# main_for_huzzah_wLED.net
KiCad netlist of a schematic drawn in EAGLE
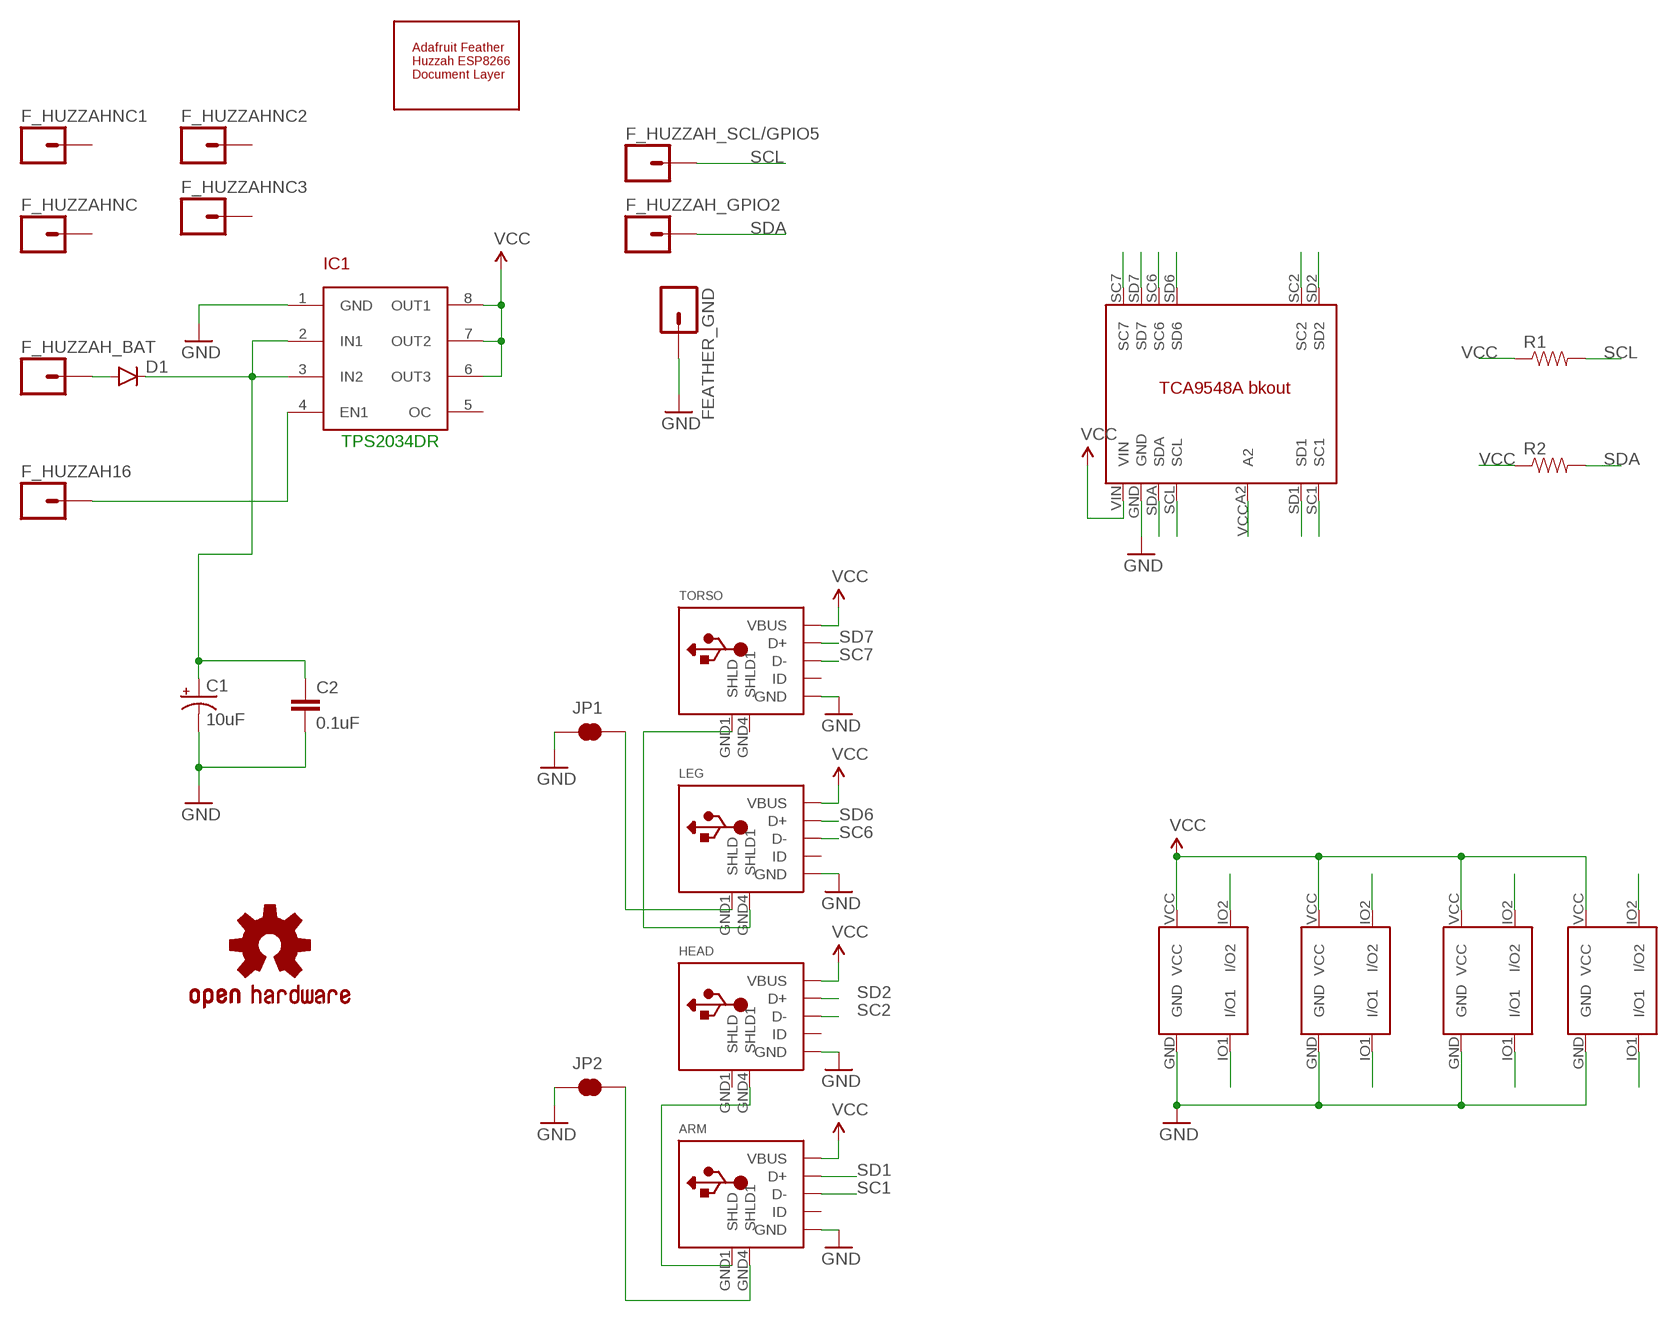
[diagram p0: schematic, sheet 1]

(export (version "E")
  (design (tool "Eeschema 10.0.6"))
  (components
    (comp (ref "ARM")
      (value "USB")
      (footprint "eagle-import:USB-MINIB-THM-MOLEX_NOSLK")
      (libsource (lib "eagle-import") (part "USB"))
    )
    (comp (ref "C1")
      (value "10uF")
      (footprint "eagle-import:CPOL-RADIAL-10UF-25V")
      (libsource (lib "eagle-import") (part "CAP_POLPTH2"))
    )
    (comp (ref "C2")
      (value "0.1uF")
      (footprint "eagle-import:CAP-PTH-SMALL")
      (libsource (lib "eagle-import") (part "CAPPTH"))
    )
    (comp (ref "D1")
      (value "DIODEKIT2")
      (footprint "eagle-import:DIODE-1N4001-KIT")
      (libsource (lib "eagle-import") (part "DIODEKIT2"))
    )
    (comp (ref "FEATHER_GND")
      (value "M01")
      (footprint "eagle-import:1X01SMALL_NS")
      (libsource (lib "eagle-import") (part "M01"))
    )
    (comp (ref "F_HUZZAH16")
      (value "M01")
      (footprint "eagle-import:1X01SMALL_NS")
      (libsource (lib "eagle-import") (part "M01"))
    )
    (comp (ref "F_HUZZAHNC")
      (value "M01")
      (footprint "eagle-import:1X01SMALL_NS")
      (libsource (lib "eagle-import") (part "M01"))
    )
    (comp (ref "F_HUZZAHNC1")
      (value "M01")
      (footprint "eagle-import:1X01SMALL_NS")
      (libsource (lib "eagle-import") (part "M01"))
    )
    (comp (ref "F_HUZZAHNC2")
      (value "M01")
      (footprint "eagle-import:1X01SMALL_NS")
      (libsource (lib "eagle-import") (part "M01"))
    )
    (comp (ref "F_HUZZAHNC3")
      (value "M01")
      (footprint "eagle-import:1X01SMALL_NS")
      (libsource (lib "eagle-import") (part "M01"))
    )
    (comp (ref "F_HUZZAH_BAT")
      (value "M01")
      (footprint "eagle-import:1X01SMALL_NS")
      (libsource (lib "eagle-import") (part "M01"))
    )
    (comp (ref "F_HUZZAH_GPIO2")
      (value "M01")
      (footprint "eagle-import:1X01SMALL_NS")
      (libsource (lib "eagle-import") (part "M01"))
    )
    (comp (ref "F_HUZZAH_SCL/GPIO5")
      (value "M01")
      (footprint "eagle-import:1X01SMALL_NS")
      (libsource (lib "eagle-import") (part "M01"))
    )
    (comp (ref "HEAD")
      (value "USB")
      (footprint "eagle-import:USB-MINIB-THM-MOLEX_NOSLK")
      (libsource (lib "eagle-import") (part "USB"))
    )
    (comp (ref "IC1")
      (value "TPS2055A")
      (footprint "eagle-import:SO-08")
      (libsource (lib "eagle-import") (part "TPS2055A"))
    )
    (comp (ref "JP1")
      (value "JUMPER-PAD-2-NC_BY_TRACENO_SILK")
      (footprint "eagle-import:PAD-JUMPER-2-NC_BY_TRACE_NO_SILK")
      (libsource (lib "eagle-import") (part "JUMPER-PAD-2-NC_BY_TRACENO_SILK"))
    )
    (comp (ref "JP2")
      (value "JUMPER-PAD-2-NC_BY_TRACENO_SILK")
      (footprint "eagle-import:PAD-JUMPER-2-NC_BY_TRACE_NO_SILK")
      (libsource (lib "eagle-import") (part "JUMPER-PAD-2-NC_BY_TRACENO_SILK"))
    )
    (comp (ref "LEG")
      (value "USB")
      (footprint "eagle-import:USB-MINIB-THM-MOLEX_NOSLK")
      (libsource (lib "eagle-import") (part "USB"))
    )
    (comp (ref "LOGO1")
      (value "OSHW-LOGOM")
      (footprint "eagle-import:OSHW-LOGO-M")
      (libsource (lib "eagle-import") (part "OSHW-LOGOM"))
    )
    (comp (ref "R1")
      (value "RESISTORAXIAL-0.3")
      (footprint "eagle-import:AXIAL-0.3")
      (libsource (lib "eagle-import") (part "RESISTORAXIAL-0.3"))
    )
    (comp (ref "R2")
      (value "RESISTORAXIAL-0.3")
      (footprint "eagle-import:AXIAL-0.3")
      (libsource (lib "eagle-import") (part "RESISTORAXIAL-0.3"))
    )
    (comp (ref "TORSO")
      (value "USB")
      (footprint "eagle-import:USB-MINIB-THM-MOLEX_NOSLK")
      (libsource (lib "eagle-import") (part "USB"))
    )
    (comp (ref "U$1")
      (value "TCA9548_MIN")
      (footprint "eagle-import:TCA9548_NOEXTRA")
      (libsource (lib "eagle-import") (part "TCA9548_MIN"))
    )
    (comp (ref "U$2")
      (value "TVS_ARRAY_CD143A")
      (footprint "eagle-import:SOT-143")
      (libsource (lib "eagle-import") (part "TVS_ARRAY_CD143A"))
    )
    (comp (ref "U$3")
      (value "TVS_ARRAY_CD143A")
      (footprint "eagle-import:SOT-143")
      (libsource (lib "eagle-import") (part "TVS_ARRAY_CD143A"))
    )
    (comp (ref "U$4")
      (value "TVS_ARRAY_CD143A")
      (footprint "eagle-import:SOT-143")
      (libsource (lib "eagle-import") (part "TVS_ARRAY_CD143A"))
    )
    (comp (ref "U$5")
      (value "TVS_ARRAY_CD143A")
      (footprint "eagle-import:SOT-143")
      (libsource (lib "eagle-import") (part "TVS_ARRAY_CD143A"))
    )
    (comp (ref "U$7")
      (value "FEATHER_HUZZAH_DOCUMENT")
      (footprint "eagle-import:FEATHER_HUZZAH_DOC_ONLY")
      (libsource (lib "eagle-import") (part "FEATHER_HUZZAH_DOCUMENT"))
    )
  )
  (nets
    (net (code "1") (name "/SC1") (class "Default")
      (node (ref "ARM") (pin "D-") (pinfunction "D-_D-") (pintype "bidirectional"))
      (node (ref "U$1") (pin "SC1") (pinfunction "SC1_SC1") (pintype "bidirectional"))
      (node (ref "U$3") (pin "IO1") (pinfunction "I/O1_IO1") (pintype "bidirectional"))
    )
    (net (code "2") (name "/SC2") (class "Default")
      (node (ref "HEAD") (pin "D-") (pinfunction "D-_D-") (pintype "bidirectional"))
      (node (ref "U$1") (pin "SC2") (pinfunction "SC2_SC2") (pintype "bidirectional"))
      (node (ref "U$2") (pin "IO1") (pinfunction "I/O1_IO1") (pintype "bidirectional"))
    )
    (net (code "3") (name "/SC6") (class "Default")
      (node (ref "LEG") (pin "D-") (pinfunction "D-_D-") (pintype "bidirectional"))
      (node (ref "U$1") (pin "SC6") (pinfunction "SC6_SC6") (pintype "bidirectional"))
      (node (ref "U$5") (pin "IO1") (pinfunction "I/O1_IO1") (pintype "bidirectional"))
    )
    (net (code "4") (name "/SC7") (class "Default")
      (node (ref "TORSO") (pin "D-") (pinfunction "D-_D-") (pintype "bidirectional"))
      (node (ref "U$1") (pin "SC7") (pinfunction "SC7_SC7") (pintype "bidirectional"))
      (node (ref "U$4") (pin "IO1") (pinfunction "I/O1_IO1") (pintype "bidirectional"))
    )
    (net (code "5") (name "/SCL") (class "Default")
      (node (ref "F_HUZZAH_SCL/GPIO5") (pin "P$1") (pinfunction "1_P$1") (pintype "passive"))
      (node (ref "R1") (pin "P$2") (pinfunction "2_P$2") (pintype "passive"))
      (node (ref "U$1") (pin "SCL") (pinfunction "SCL_SCL") (pintype "bidirectional"))
    )
    (net (code "6") (name "/SD1") (class "Default")
      (node (ref "ARM") (pin "D+") (pinfunction "D+_D+") (pintype "bidirectional"))
      (node (ref "U$1") (pin "SD1") (pinfunction "SD1_SD1") (pintype "bidirectional"))
      (node (ref "U$3") (pin "IO2") (pinfunction "I/O2_IO2") (pintype "bidirectional"))
    )
    (net (code "7") (name "/SD2") (class "Default")
      (node (ref "HEAD") (pin "D+") (pinfunction "D+_D+") (pintype "bidirectional"))
      (node (ref "U$1") (pin "SD2") (pinfunction "SD2_SD2") (pintype "bidirectional"))
      (node (ref "U$2") (pin "IO2") (pinfunction "I/O2_IO2") (pintype "bidirectional"))
    )
    (net (code "8") (name "/SD6") (class "Default")
      (node (ref "LEG") (pin "D+") (pinfunction "D+_D+") (pintype "bidirectional"))
      (node (ref "U$1") (pin "SD6") (pinfunction "SD6_SD6") (pintype "bidirectional"))
      (node (ref "U$5") (pin "IO2") (pinfunction "I/O2_IO2") (pintype "bidirectional"))
    )
    (net (code "9") (name "/SD7") (class "Default")
      (node (ref "TORSO") (pin "D+") (pinfunction "D+_D+") (pintype "bidirectional"))
      (node (ref "U$1") (pin "SD7") (pinfunction "SD7_SD7") (pintype "bidirectional"))
      (node (ref "U$4") (pin "IO2") (pinfunction "I/O2_IO2") (pintype "bidirectional"))
    )
    (net (code "10") (name "/SDA") (class "Default")
      (node (ref "F_HUZZAH_GPIO2") (pin "P$1") (pinfunction "1_P$1") (pintype "passive"))
      (node (ref "R2") (pin "P$2") (pinfunction "2_P$2") (pintype "passive"))
      (node (ref "U$1") (pin "SDA") (pinfunction "SDA_SDA") (pintype "bidirectional"))
    )
    (net (code "11") (name "GND") (class "Default")
      (node (ref "ARM") (pin "GND") (pinfunction "GND_GND") (pintype "power_in"))
      (node (ref "C1") (pin "2") (pinfunction "-_2") (pintype "passive"))
      (node (ref "C2") (pin "2") (pinfunction "2_2") (pintype "passive"))
      (node (ref "FEATHER_GND") (pin "P$1") (pinfunction "1_P$1") (pintype "passive"))
      (node (ref "HEAD") (pin "GND") (pinfunction "GND_GND") (pintype "power_in"))
      (node (ref "IC1") (pin "1") (pinfunction "GND_1") (pintype "power_in"))
      (node (ref "JP1") (pin "1") (pinfunction "1_1") (pintype "passive"))
      (node (ref "JP2") (pin "1") (pinfunction "1_1") (pintype "passive"))
      (node (ref "LEG") (pin "GND") (pinfunction "GND_GND") (pintype "power_in"))
      (node (ref "TORSO") (pin "GND") (pinfunction "GND_GND") (pintype "power_in"))
      (node (ref "U$1") (pin "GND") (pinfunction "GND_GND") (pintype "bidirectional"))
      (node (ref "U$2") (pin "GND") (pinfunction "GND_GND") (pintype "power_in"))
      (node (ref "U$3") (pin "GND") (pinfunction "GND_GND") (pintype "power_in"))
      (node (ref "U$4") (pin "GND") (pinfunction "GND_GND") (pintype "power_in"))
      (node (ref "U$5") (pin "GND") (pinfunction "GND_GND") (pintype "power_in"))
    )
    (net (code "12") (name "Net-(ARM-SHLD)") (class "Default")
      (node (ref "ARM") (pin "GND1") (pinfunction "SHLD_GND1") (pintype "bidirectional"))
      (node (ref "HEAD") (pin "GND4") (pinfunction "SHLD1_GND4") (pintype "bidirectional"))
    )
    (net (code "13") (name "Net-(ARM-SHLD1)") (class "Default")
      (node (ref "ARM") (pin "GND4") (pinfunction "SHLD1_GND4") (pintype "bidirectional"))
      (node (ref "JP2") (pin "2") (pinfunction "2_2") (pintype "passive"))
    )
    (net (code "14") (name "Net-(C1-+)") (class "Default")
      (node (ref "C1") (pin "1") (pinfunction "+_1") (pintype "passive"))
      (node (ref "C2") (pin "1") (pinfunction "1_1") (pintype "passive"))
      (node (ref "D1") (pin "C") (pinfunction "C_C") (pintype "passive"))
      (node (ref "IC1") (pin "2") (pinfunction "IN1_2") (pintype "power_in"))
      (node (ref "IC1") (pin "3") (pinfunction "IN2_3") (pintype "power_in"))
    )
    (net (code "15") (name "Net-(F_HUZZAH16-1)") (class "Default")
      (node (ref "F_HUZZAH16") (pin "P$1") (pinfunction "1_P$1") (pintype "passive"))
      (node (ref "IC1") (pin "4") (pinfunction "EN1_4") (pintype "output"))
    )
    (net (code "16") (name "Net-(F_HUZZAH_BAT-1)") (class "Default")
      (node (ref "D1") (pin "A") (pinfunction "A_A") (pintype "passive"))
      (node (ref "F_HUZZAH_BAT") (pin "P$1") (pinfunction "1_P$1") (pintype "passive"))
    )
    (net (code "17") (name "Net-(LEG-SHLD)") (class "Default")
      (node (ref "JP1") (pin "2") (pinfunction "2_2") (pintype "passive"))
      (node (ref "LEG") (pin "GND1") (pinfunction "SHLD_GND1") (pintype "bidirectional"))
    )
    (net (code "18") (name "Net-(LEG-SHLD1)") (class "Default")
      (node (ref "LEG") (pin "GND4") (pinfunction "SHLD1_GND4") (pintype "bidirectional"))
      (node (ref "TORSO") (pin "GND1") (pinfunction "SHLD_GND1") (pintype "bidirectional"))
    )
    (net (code "19") (name "VCC") (class "Default")
      (node (ref "ARM") (pin "VBUS") (pinfunction "VBUS_VBUS") (pintype "power_in"))
      (node (ref "HEAD") (pin "VBUS") (pinfunction "VBUS_VBUS") (pintype "power_in"))
      (node (ref "IC1") (pin "6") (pinfunction "OUT3_6") (pintype "power_in"))
      (node (ref "IC1") (pin "7") (pinfunction "OUT2_7") (pintype "power_in"))
      (node (ref "IC1") (pin "8") (pinfunction "OUT1_8") (pintype "power_in"))
      (node (ref "LEG") (pin "VBUS") (pinfunction "VBUS_VBUS") (pintype "power_in"))
      (node (ref "R1") (pin "P$1") (pinfunction "1_P$1") (pintype "passive"))
      (node (ref "R2") (pin "P$1") (pinfunction "1_P$1") (pintype "passive"))
      (node (ref "TORSO") (pin "VBUS") (pinfunction "VBUS_VBUS") (pintype "power_in"))
      (node (ref "U$1") (pin "A2") (pinfunction "A2_A2") (pintype "bidirectional"))
      (node (ref "U$1") (pin "VIN") (pinfunction "VIN_VIN") (pintype "bidirectional"))
      (node (ref "U$2") (pin "VCC") (pinfunction "VCC_VCC") (pintype "power_in"))
      (node (ref "U$3") (pin "VCC") (pinfunction "VCC_VCC") (pintype "power_in"))
      (node (ref "U$4") (pin "VCC") (pinfunction "VCC_VCC") (pintype "power_in"))
      (node (ref "U$5") (pin "VCC") (pinfunction "VCC_VCC") (pintype "power_in"))
    )
    (net (code "20") (name "unconnected-(ARM-PadID)") (class "Default")
      (node (ref "ARM") (pin "ID") (pinfunction "ID_ID") (pintype "bidirectional"))
    )
    (net (code "21") (name "unconnected-(F_HUZZAHNC-1-PadP$1)") (class "Default")
      (node (ref "F_HUZZAHNC") (pin "P$1") (pinfunction "1_P$1") (pintype "passive"))
    )
    (net (code "22") (name "unconnected-(F_HUZZAHNC1-1-PadP$1)") (class "Default")
      (node (ref "F_HUZZAHNC1") (pin "P$1") (pinfunction "1_P$1") (pintype "passive"))
    )
    (net (code "23") (name "unconnected-(F_HUZZAHNC2-1-PadP$1)") (class "Default")
      (node (ref "F_HUZZAHNC2") (pin "P$1") (pinfunction "1_P$1") (pintype "passive"))
    )
    (net (code "24") (name "unconnected-(F_HUZZAHNC3-1-PadP$1)") (class "Default")
      (node (ref "F_HUZZAHNC3") (pin "P$1") (pinfunction "1_P$1") (pintype "passive"))
    )
    (net (code "25") (name "unconnected-(HEAD-PadID)") (class "Default")
      (node (ref "HEAD") (pin "ID") (pinfunction "ID_ID") (pintype "bidirectional"))
    )
    (net (code "26") (name "unconnected-(HEAD-SHLD-PadGND1)") (class "Default")
      (node (ref "HEAD") (pin "GND1") (pinfunction "SHLD_GND1") (pintype "bidirectional"))
    )
    (net (code "27") (name "unconnected-(IC1-OC-Pad5)") (class "Default")
      (node (ref "IC1") (pin "5") (pinfunction "OC_5") (pintype "output"))
    )
    (net (code "28") (name "unconnected-(LEG-PadID)") (class "Default")
      (node (ref "LEG") (pin "ID") (pinfunction "ID_ID") (pintype "bidirectional"))
    )
    (net (code "29") (name "unconnected-(TORSO-PadID)") (class "Default")
      (node (ref "TORSO") (pin "ID") (pinfunction "ID_ID") (pintype "bidirectional"))
    )
    (net (code "30") (name "unconnected-(TORSO-SHLD1-PadGND4)") (class "Default")
      (node (ref "TORSO") (pin "GND4") (pinfunction "SHLD1_GND4") (pintype "bidirectional"))
    )
  )
)
